# PCB-CCU-IRISCTRL_ETHERMEGA.net
KiCad netlist of a schematic drawn in EAGLE
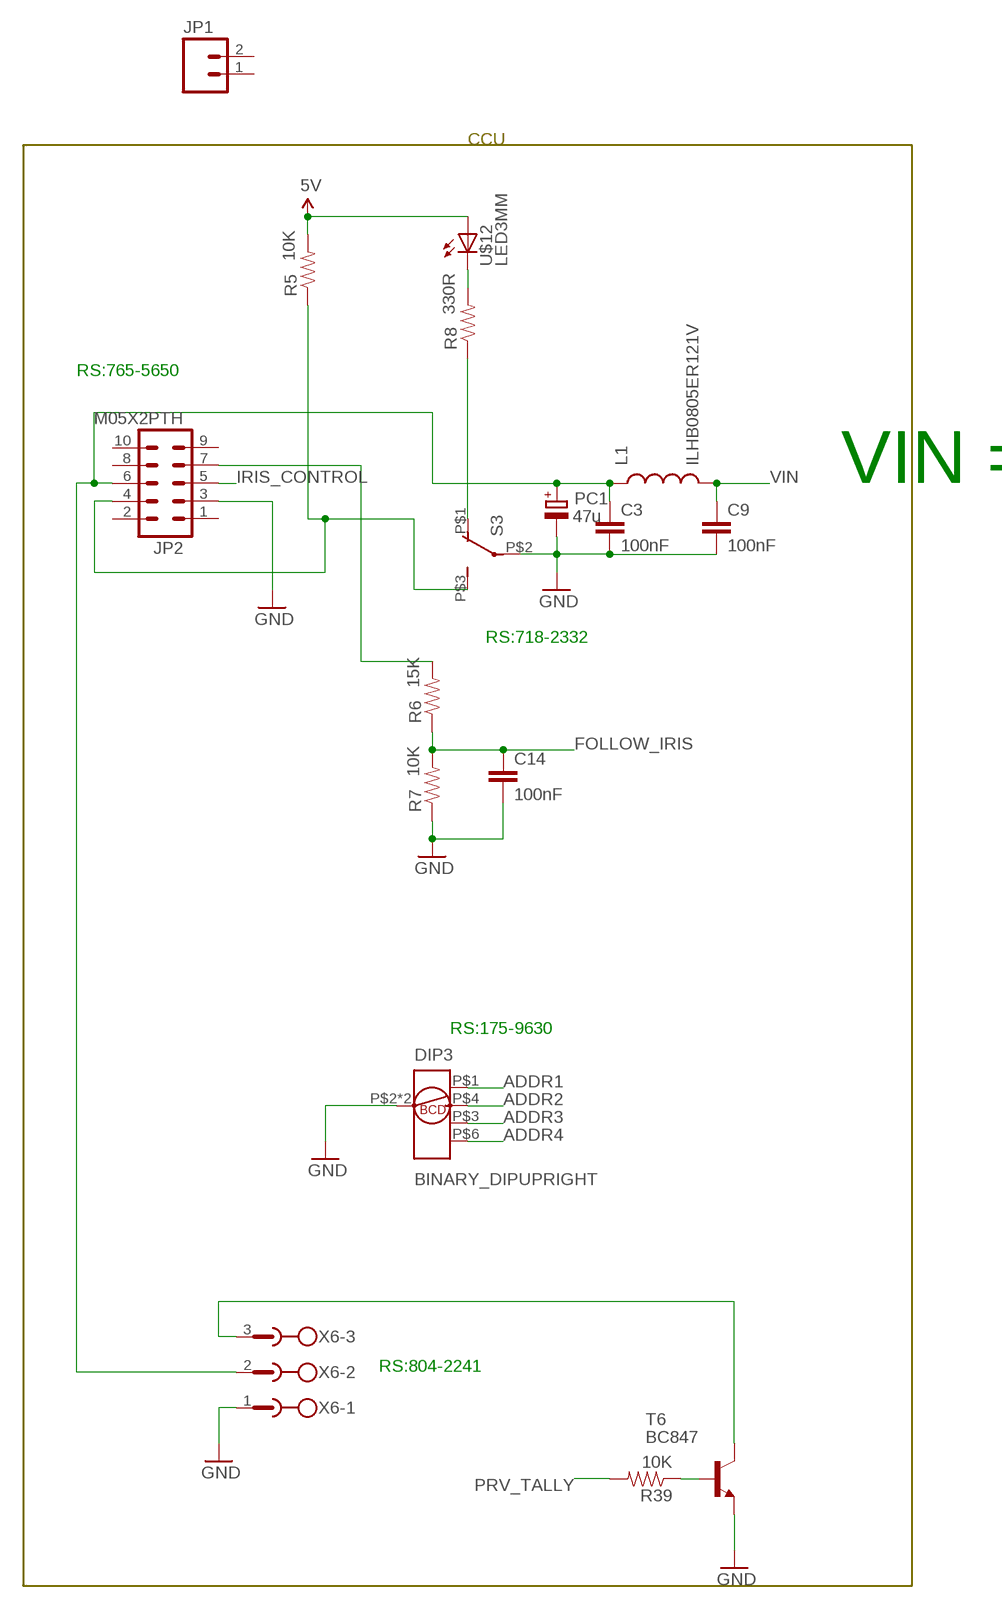
[diagram p0: schematic, sheet 1, part 1 of 3]
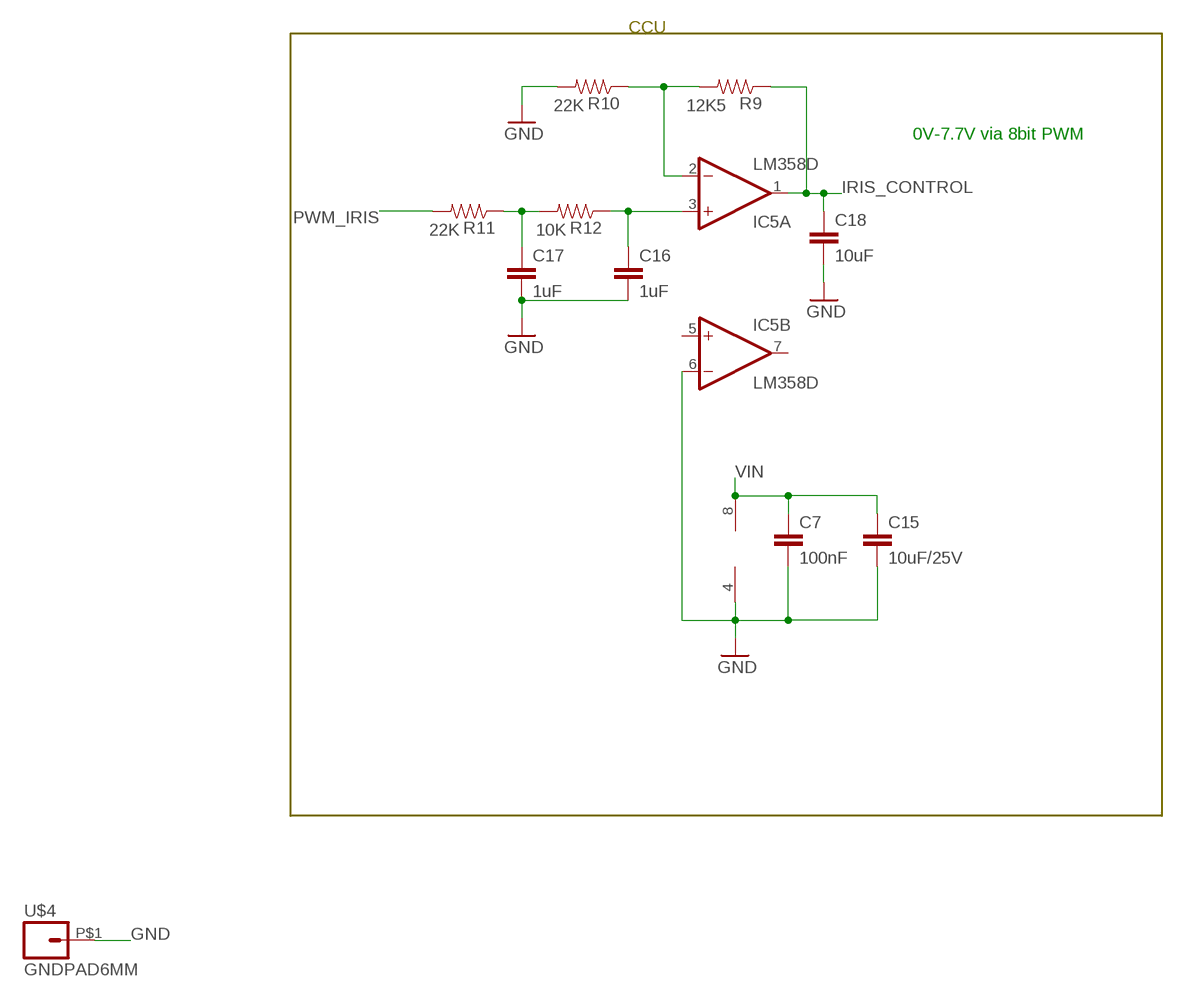
[diagram p1: schematic, sheet 1, part 2 of 3]
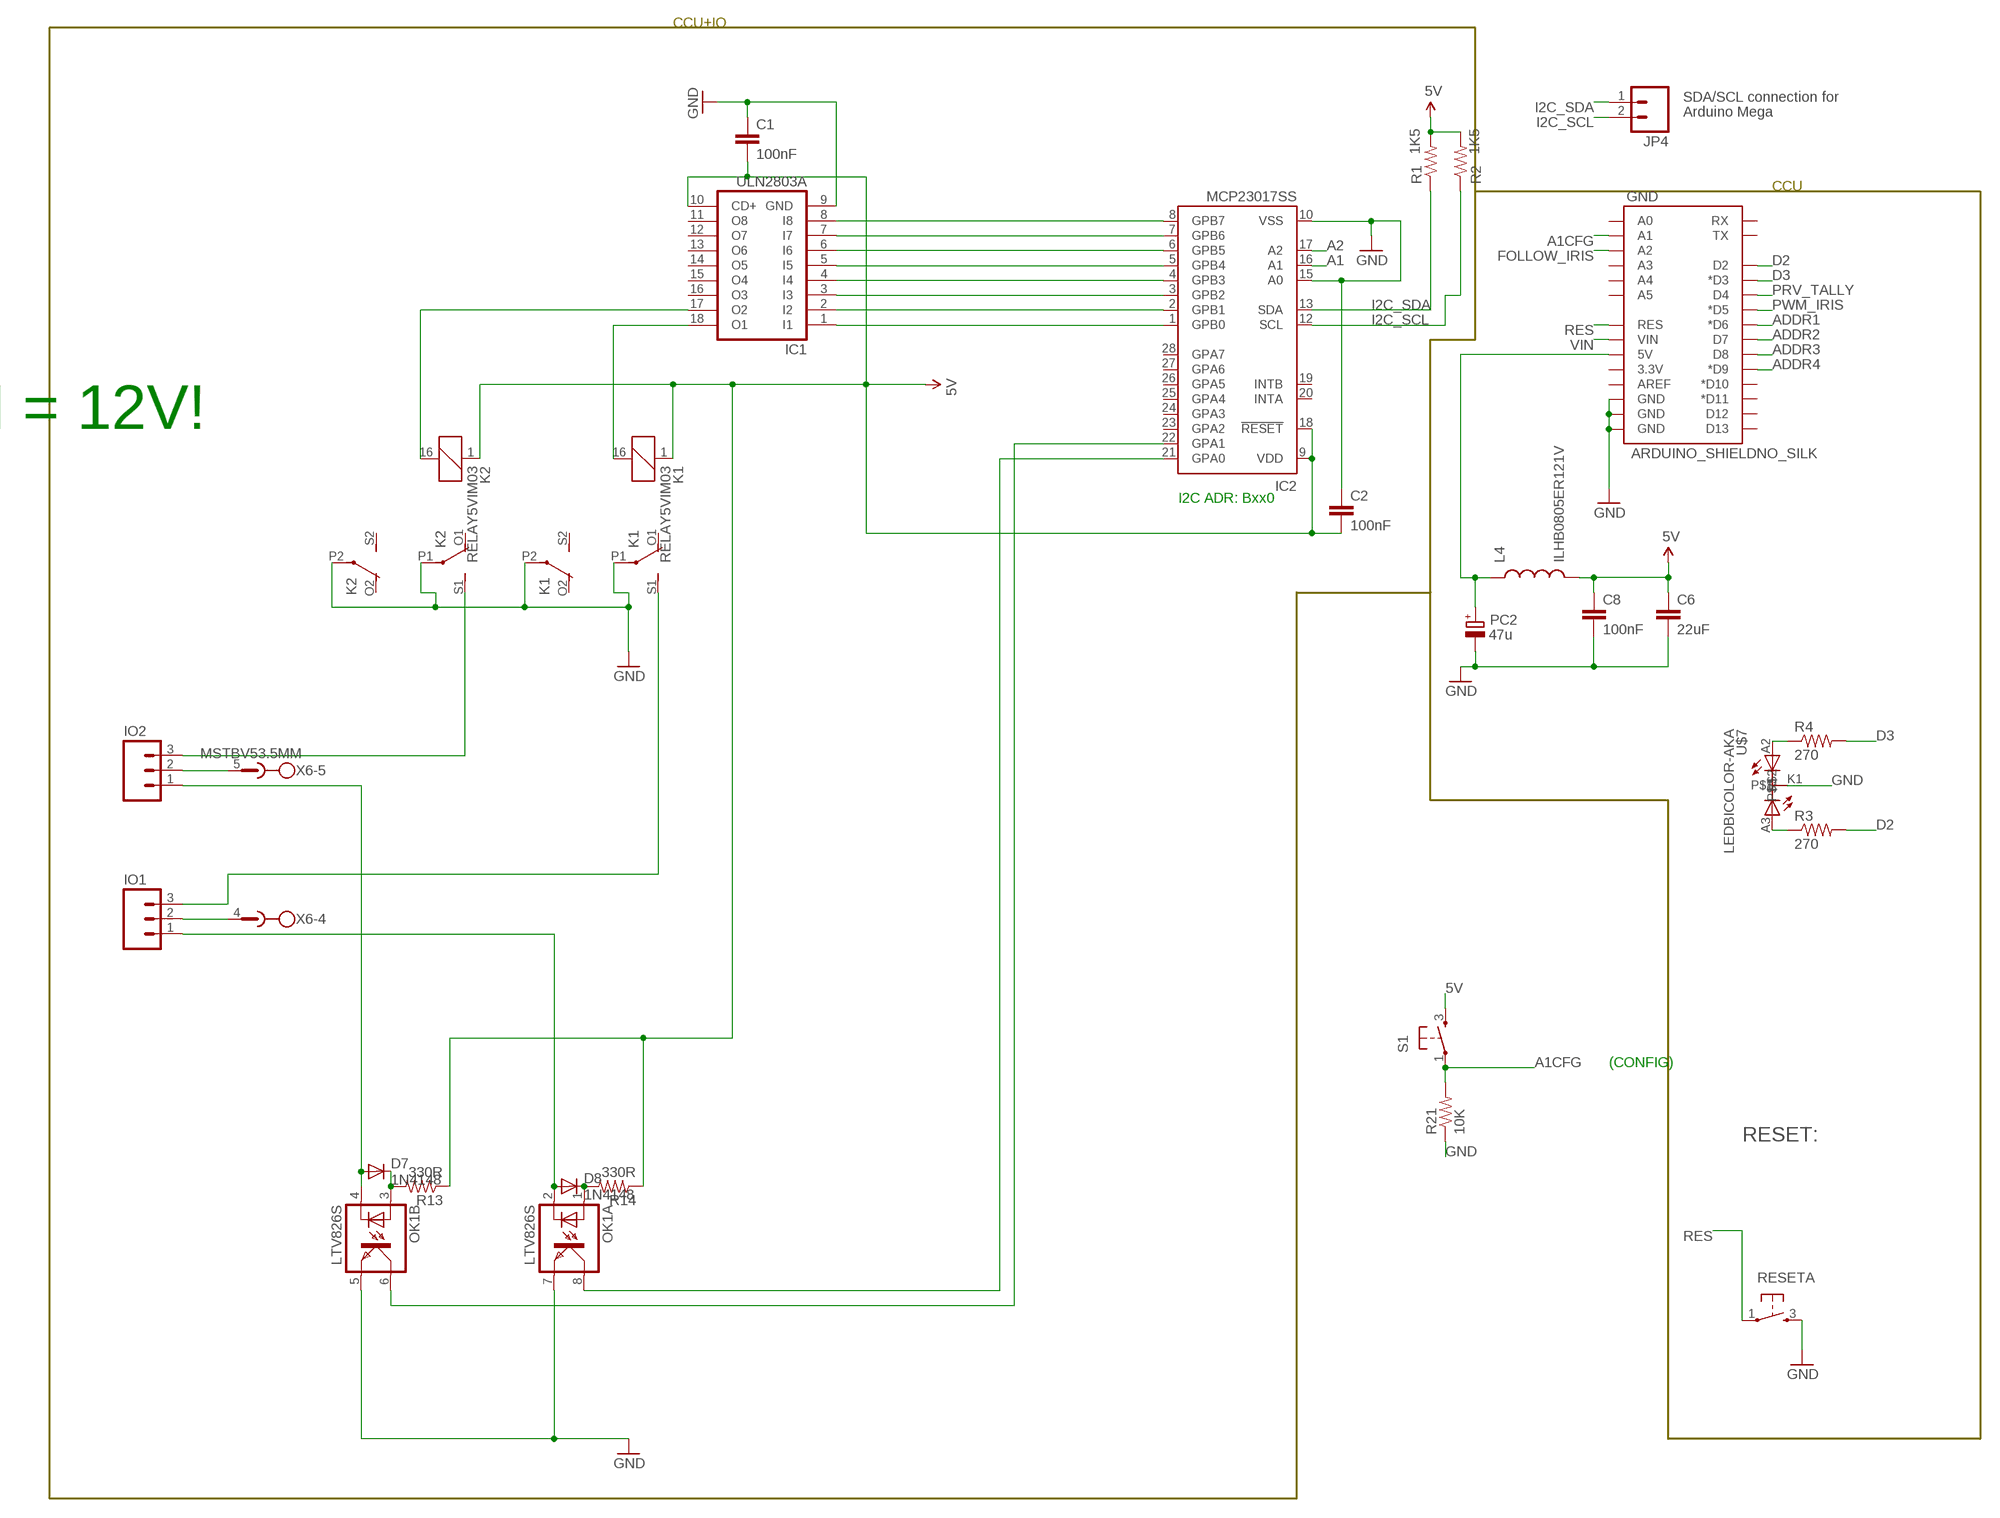
[diagram p2: schematic, sheet 1, part 3 of 3]

(export (version "E")
  (design (tool "Eeschema 10.0.6"))
  (components
    (comp (ref "C1")
      (value "100nF")
      (footprint "eagle-import:0805")
      (libsource (lib "eagle-import") (part "CAP0805"))
    )
    (comp (ref "C2")
      (value "100nF")
      (footprint "eagle-import:0603-CAP")
      (libsource (lib "eagle-import") (part "CAP0603-CAP"))
    )
    (comp (ref "C3")
      (value "100nF")
      (footprint "eagle-import:0603-CAP")
      (libsource (lib "eagle-import") (part "CAP0603-CAP"))
    )
    (comp (ref "C6")
      (value "22uF")
      (footprint "eagle-import:0805")
      (libsource (lib "eagle-import") (part "CAP0805"))
    )
    (comp (ref "C7")
      (value "100nF")
      (footprint "eagle-import:0603-CAP")
      (libsource (lib "eagle-import") (part "CAP0603-CAP"))
    )
    (comp (ref "C8")
      (value "100nF")
      (footprint "eagle-import:0603-CAP")
      (libsource (lib "eagle-import") (part "CAP0603-CAP"))
    )
    (comp (ref "C9")
      (value "100nF")
      (footprint "eagle-import:0603-CAP")
      (libsource (lib "eagle-import") (part "CAP0603-CAP"))
    )
    (comp (ref "C14")
      (value "100nF")
      (footprint "eagle-import:0603-CAP")
      (libsource (lib "eagle-import") (part "CAP0603-CAP"))
    )
    (comp (ref "C15")
      (value "10uF/25V")
      (footprint "eagle-import:0805")
      (libsource (lib "eagle-import") (part "CAP0805"))
    )
    (comp (ref "C16")
      (value "1uF")
      (footprint "eagle-import:0805")
      (libsource (lib "eagle-import") (part "CAP0805"))
    )
    (comp (ref "C17")
      (value "1uF")
      (footprint "eagle-import:0805")
      (libsource (lib "eagle-import") (part "CAP0805"))
    )
    (comp (ref "C18")
      (value "10uF")
      (footprint "eagle-import:0805")
      (libsource (lib "eagle-import") (part "CAP0805"))
    )
    (comp (ref "D7")
      (value "1N4148")
      (footprint "eagle-import:SOD-323")
      (libsource (lib "eagle-import") (part "DIODESOD"))
    )
    (comp (ref "D8")
      (value "1N4148")
      (footprint "eagle-import:SOD-323")
      (libsource (lib "eagle-import") (part "DIODESOD"))
    )
    (comp (ref "DIP3")
      (value "BINARY_DIPUPRIGHT")
      (footprint "eagle-import:P65SMT_UPRIGHT_TH")
      (libsource (lib "eagle-import") (part "BINARY_DIPUPRIGHT"))
    )
    (comp (ref "GND")
      (value "ARDUINO_SHIELDNO_SILK")
      (footprint "eagle-import:DUEMILANOVE_VIAS")
      (libsource (lib "eagle-import") (part "ARDUINO_SHIELDNO_SILK"))
    )
    (comp (ref "IC1")
      (value "ULN2803A")
      (footprint "eagle-import:SO18W")
      (libsource (lib "eagle-import") (part "ULN2803ASO18W"))
    )
    (comp (ref "IC2")
      (value "MCP23017SS")
      (footprint "eagle-import:SSOP28")
      (fields (field (name "MF") "MICROCHIP") (field (name "MPN") "MCP23017-E/SS"))
      (libsource (lib "eagle-import") (part "MCP23017SS"))
    )
    (comp (ref "IC5")
      (value "LM358D")
      (footprint "eagle-import:SO08")
      (libsource (lib "eagle-import") (part "LM358D"))
    )
    (comp (ref "IO1")
      (value "M03LOCK")
      (footprint "eagle-import:1X03_LOCK")
      (libsource (lib "eagle-import") (part "M03LOCK"))
    )
    (comp (ref "IO2")
      (value "M03LOCK")
      (footprint "eagle-import:1X03_LOCK")
      (libsource (lib "eagle-import") (part "M03LOCK"))
    )
    (comp (ref "JP1")
      (value "M02PTH")
      (footprint "eagle-import:1X02")
      (libsource (lib "eagle-import") (part "M02PTH"))
    )
    (comp (ref "JP2")
      (value "M05X2PTH")
      (footprint "eagle-import:AVR_ICSP")
      (libsource (lib "eagle-import") (part "M05X2PTH"))
    )
    (comp (ref "JP4")
      (value "M02PTH")
      (footprint "eagle-import:1X02")
      (libsource (lib "eagle-import") (part "M02PTH"))
    )
    (comp (ref "K1")
      (value "RELAY5VIM03")
      (footprint "eagle-import:DS2Y")
      (libsource (lib "eagle-import") (part "RELAY5VIM03"))
    )
    (comp (ref "K2")
      (value "RELAY5VIM03")
      (footprint "eagle-import:DS2Y")
      (libsource (lib "eagle-import") (part "RELAY5VIM03"))
    )
    (comp (ref "L1")
      (value "ILHB0805ER121V")
      (footprint "eagle-import:0805")
      (libsource (lib "eagle-import") (part "INDUCTOR0805"))
    )
    (comp (ref "L4")
      (value "ILHB0805ER121V")
      (footprint "eagle-import:0805")
      (libsource (lib "eagle-import") (part "INDUCTOR0805"))
    )
    (comp (ref "OK1")
      (value "LTV826S")
      (footprint "eagle-import:DIL8-SMD")
      (libsource (lib "eagle-import") (part "LTV826S"))
    )
    (comp (ref "PC1")
      (value "47u")
      (footprint "eagle-import:PANASONIC_D")
      (libsource (lib "eagle-import") (part "CPOL-EUD"))
    )
    (comp (ref "PC2")
      (value "47u")
      (footprint "eagle-import:PANASONIC_D")
      (libsource (lib "eagle-import") (part "CPOL-EUD"))
    )
    (comp (ref "R1")
      (value "1K5")
      (footprint "eagle-import:0603-RES")
      (libsource (lib "eagle-import") (part "RESISTOR0603-RES"))
    )
    (comp (ref "R2")
      (value "1K5")
      (footprint "eagle-import:0603-RES")
      (libsource (lib "eagle-import") (part "RESISTOR0603-RES"))
    )
    (comp (ref "R3")
      (value "270")
      (footprint "eagle-import:0603-RES")
      (libsource (lib "eagle-import") (part "RESISTOR0603-RES"))
    )
    (comp (ref "R4")
      (value "270")
      (footprint "eagle-import:0603-RES")
      (libsource (lib "eagle-import") (part "RESISTOR0603-RES"))
    )
    (comp (ref "R5")
      (value "10K")
      (footprint "eagle-import:0603-RES")
      (libsource (lib "eagle-import") (part "RESISTOR0603-RES"))
    )
    (comp (ref "R6")
      (value "15K")
      (footprint "eagle-import:0603-RES")
      (libsource (lib "eagle-import") (part "RESISTOR0603-RES"))
    )
    (comp (ref "R7")
      (value "10K")
      (footprint "eagle-import:0603-RES")
      (libsource (lib "eagle-import") (part "RESISTOR0603-RES"))
    )
    (comp (ref "R8")
      (value "330R")
      (footprint "eagle-import:0603-RES")
      (libsource (lib "eagle-import") (part "RESISTOR0603-RES"))
    )
    (comp (ref "R9")
      (value "12K5")
      (footprint "eagle-import:0603-RES")
      (libsource (lib "eagle-import") (part "RESISTOR0603-RES"))
    )
    (comp (ref "R10")
      (value "22K")
      (footprint "eagle-import:0603-RES")
      (libsource (lib "eagle-import") (part "RESISTOR0603-RES"))
    )
    (comp (ref "R11")
      (value "22K")
      (footprint "eagle-import:0603-RES")
      (libsource (lib "eagle-import") (part "RESISTOR0603-RES"))
    )
    (comp (ref "R12")
      (value "10K")
      (footprint "eagle-import:0603-RES")
      (libsource (lib "eagle-import") (part "RESISTOR0603-RES"))
    )
    (comp (ref "R13")
      (value "330R")
      (footprint "eagle-import:0603-RES")
      (libsource (lib "eagle-import") (part "RESISTOR0603-RES"))
    )
    (comp (ref "R14")
      (value "330R")
      (footprint "eagle-import:0603-RES")
      (libsource (lib "eagle-import") (part "RESISTOR0603-RES"))
    )
    (comp (ref "R21")
      (value "10K")
      (footprint "eagle-import:0603-RES")
      (libsource (lib "eagle-import") (part "RESISTOR0603-RES"))
    )
    (comp (ref "R39")
      (value "10K")
      (footprint "eagle-import:0603-RES")
      (libsource (lib "eagle-import") (part "RESISTOR0603-RES"))
    )
    (comp (ref "RESETA")
      (value "TAC_SWITCH")
      (footprint "eagle-import:PUSHBUTTON")
      (libsource (lib "eagle-import") (part "TAC_SWITCH"))
    )
    (comp (ref "S1")
      (value "TAC_SWITCH")
      (footprint "eagle-import:PUSHBUTTON")
      (libsource (lib "eagle-import") (part "TAC_SWITCH"))
    )
    (comp (ref "S3")
      (value "SWITCH-DPST")
      (footprint "eagle-import:TECONNECTIVITY-DPST")
      (libsource (lib "eagle-import") (part "SWITCH-DPST"))
    )
    (comp (ref "T6")
      (value "BC847")
      (footprint "eagle-import:SOT23")
      (libsource (lib "eagle-import") (part "BC847"))
    )
    (comp (ref "U$4")
      (value "GNDPAD6MM")
      (footprint "eagle-import:3.2MMPAD6MM")
      (libsource (lib "eagle-import") (part "GNDPAD6MM"))
    )
    (comp (ref "U$7")
      (value "LEDBICOLOR-AKA")
      (footprint "eagle-import:LED5MM-BICOLOR")
      (libsource (lib "eagle-import") (part "LEDBICOLOR-AKA"))
    )
    (comp (ref "U$12")
      (value "LED3MM")
      (footprint "eagle-import:LED3MM")
      (libsource (lib "eagle-import") (part "LED3MM"))
    )
    (comp (ref "X6")
      (value "MSTBV53.5MM")
      (footprint "eagle-import:MSTBV5-3.5")
      (libsource (lib "eagle-import") (part "MSTBV53.5MM"))
    )
  )
  (nets
    (net (code "1") (name "5V") (class "Default")
      (node (ref "C1") (pin "2") (pinfunction "2_2") (pintype "passive"))
      (node (ref "C2") (pin "2") (pinfunction "2_2") (pintype "passive"))
      (node (ref "C6") (pin "1") (pinfunction "1_1") (pintype "passive"))
      (node (ref "C8") (pin "1") (pinfunction "1_1") (pintype "passive"))
      (node (ref "IC1") (pin "10") (pinfunction "CD+_10") (pintype "passive"))
      (node (ref "IC2") (pin "18") (pinfunction "~{RESET}_18") (pintype "input"))
      (node (ref "IC2") (pin "9") (pinfunction "VDD_9") (pintype "power_in"))
      (node (ref "K1") (pin "1") (pinfunction "1_1") (pintype "passive"))
      (node (ref "K2") (pin "1") (pinfunction "1_1") (pintype "passive"))
      (node (ref "L4") (pin "2") (pinfunction "2_2") (pintype "passive"))
      (node (ref "R1") (pin "2") (pinfunction "2_2") (pintype "passive"))
      (node (ref "R13") (pin "1") (pinfunction "1_1") (pintype "passive"))
      (node (ref "R14") (pin "1") (pinfunction "1_1") (pintype "passive"))
      (node (ref "R2") (pin "2") (pinfunction "2_2") (pintype "passive"))
      (node (ref "R5") (pin "2") (pinfunction "2_2") (pintype "passive"))
      (node (ref "S1") (pin "3") (pinfunction "3_3") (pintype "passive"))
      (node (ref "U$12") (pin "A") (pinfunction "A_A") (pintype "passive"))
    )
    (net (code "2") (name "A1") (class "Default")
      (node (ref "IC2") (pin "16") (pinfunction "A1_16") (pintype "input"))
    )
    (net (code "3") (name "A1CFG") (class "Default")
      (node (ref "GND") (pin "A1") (pinfunction "A1_A1") (pintype "bidirectional"))
      (node (ref "R21") (pin "2") (pinfunction "2_2") (pintype "passive"))
      (node (ref "S1") (pin "1") (pinfunction "1_1") (pintype "passive"))
    )
    (net (code "4") (name "A2") (class "Default")
      (node (ref "IC2") (pin "17") (pinfunction "A2_17") (pintype "input"))
    )
    (net (code "5") (name "ADDR1") (class "Default")
      (node (ref "DIP3") (pin "P$1") (pinfunction "1_P$1") (pintype "passive"))
      (node (ref "GND") (pin "D6") (pinfunction "*D6_D6") (pintype "bidirectional"))
    )
    (net (code "6") (name "ADDR2") (class "Default")
      (node (ref "DIP3") (pin "P$4") (pinfunction "2_P$4") (pintype "passive"))
      (node (ref "GND") (pin "D7") (pinfunction "D7_D7") (pintype "bidirectional"))
    )
    (net (code "7") (name "ADDR3") (class "Default")
      (node (ref "DIP3") (pin "P$3") (pinfunction "4_P$3") (pintype "passive"))
      (node (ref "GND") (pin "D8") (pinfunction "D8_D8") (pintype "bidirectional"))
    )
    (net (code "8") (name "ADDR4") (class "Default")
      (node (ref "DIP3") (pin "P$6") (pinfunction "8_P$6") (pintype "passive"))
      (node (ref "GND") (pin "D9") (pinfunction "*D9_D9") (pintype "bidirectional"))
    )
    (net (code "9") (name "D2") (class "Default")
      (node (ref "GND") (pin "D2") (pinfunction "D2_D2") (pintype "bidirectional"))
      (node (ref "R3") (pin "2") (pinfunction "2_2") (pintype "passive"))
    )
    (net (code "10") (name "D3") (class "Default")
      (node (ref "GND") (pin "D3") (pinfunction "*D3_D3") (pintype "bidirectional"))
      (node (ref "R4") (pin "2") (pinfunction "2_2") (pintype "passive"))
    )
    (net (code "11") (name "FOLLOW_IRIS") (class "Default")
      (node (ref "C14") (pin "1") (pinfunction "1_1") (pintype "passive"))
      (node (ref "GND") (pin "A2") (pinfunction "A2_A2") (pintype "bidirectional"))
      (node (ref "R6") (pin "1") (pinfunction "1_1") (pintype "passive"))
      (node (ref "R7") (pin "2") (pinfunction "2_2") (pintype "passive"))
    )
    (net (code "12") (name "GND") (class "Default")
      (node (ref "C1") (pin "1") (pinfunction "1_1") (pintype "passive"))
      (node (ref "C14") (pin "2") (pinfunction "2_2") (pintype "passive"))
      (node (ref "C15") (pin "2") (pinfunction "2_2") (pintype "passive"))
      (node (ref "C16") (pin "2") (pinfunction "2_2") (pintype "passive"))
      (node (ref "C17") (pin "2") (pinfunction "2_2") (pintype "passive"))
      (node (ref "C18") (pin "2") (pinfunction "2_2") (pintype "passive"))
      (node (ref "C2") (pin "1") (pinfunction "1_1") (pintype "passive"))
      (node (ref "C3") (pin "2") (pinfunction "2_2") (pintype "passive"))
      (node (ref "C6") (pin "2") (pinfunction "2_2") (pintype "passive"))
      (node (ref "C7") (pin "2") (pinfunction "2_2") (pintype "passive"))
      (node (ref "C8") (pin "2") (pinfunction "2_2") (pintype "passive"))
      (node (ref "C9") (pin "2") (pinfunction "2_2") (pintype "passive"))
      (node (ref "DIP3") (pin "P$2") (pinfunction "GND_P$2") (pintype "passive"))
      (node (ref "DIP3") (pin "P$5") (pinfunction "GND_P$5") (pintype "passive"))
      (node (ref "GND") (pin "GND@0") (pinfunction "GND_GND@0") (pintype "bidirectional"))
      (node (ref "GND") (pin "GND@1") (pinfunction "GND_GND@1") (pintype "bidirectional"))
      (node (ref "GND") (pin "GND@2") (pinfunction "GND_GND@2") (pintype "bidirectional"))
      (node (ref "IC1") (pin "9") (pinfunction "GND_9") (pintype "power_in"))
      (node (ref "IC2") (pin "10") (pinfunction "VSS_10") (pintype "power_in"))
      (node (ref "IC2") (pin "15") (pinfunction "A0_15") (pintype "input"))
      (node (ref "IC5") (pin "4") (pinfunction "V-_4") (pintype "power_in"))
      (node (ref "IC5") (pin "6") (pinfunction "-IN_6") (pintype "input"))
      (node (ref "JP2") (pin "3") (pinfunction "3_3") (pintype "passive"))
      (node (ref "K1") (pin "P1") (pinfunction "P_P1") (pintype "passive"))
      (node (ref "K1") (pin "P2") (pinfunction "P_P2") (pintype "passive"))
      (node (ref "K2") (pin "P1") (pinfunction "P_P1") (pintype "passive"))
      (node (ref "K2") (pin "P2") (pinfunction "P_P2") (pintype "passive"))
      (node (ref "OK1") (pin "5") (pinfunction "EMIT_5") (pintype "passive"))
      (node (ref "OK1") (pin "7") (pinfunction "EMIT_7") (pintype "passive"))
      (node (ref "PC1") (pin "-") (pinfunction "-_-") (pintype "passive"))
      (node (ref "PC2") (pin "-") (pinfunction "-_-") (pintype "passive"))
      (node (ref "R10") (pin "2") (pinfunction "2_2") (pintype "passive"))
      (node (ref "R21") (pin "1") (pinfunction "1_1") (pintype "passive"))
      (node (ref "R7") (pin "1") (pinfunction "1_1") (pintype "passive"))
      (node (ref "RESETA") (pin "3") (pinfunction "3_3") (pintype "passive"))
      (node (ref "S3") (pin "P$2") (pinfunction "P_P$2") (pintype "passive"))
      (node (ref "T6") (pin "2") (pinfunction "E_2") (pintype "passive"))
      (node (ref "U$4") (pin "P$1") (pinfunction "1_P$1") (pintype "passive"))
      (node (ref "U$7") (pin "K1") (pinfunction "P$1_K1") (pintype "bidirectional"))
      (node (ref "X6") (pin "1") (pinfunction "1_1") (pintype "passive"))
    )
    (net (code "13") (name "I2C_SCL") (class "Default")
      (node (ref "IC2") (pin "12") (pinfunction "SCL_12") (pintype "input"))
      (node (ref "JP4") (pin "2") (pinfunction "2_2") (pintype "passive"))
      (node (ref "R2") (pin "1") (pinfunction "1_1") (pintype "passive"))
    )
    (net (code "14") (name "I2C_SDA") (class "Default")
      (node (ref "IC2") (pin "13") (pinfunction "SDA_13") (pintype "bidirectional"))
      (node (ref "JP4") (pin "1") (pinfunction "1_1") (pintype "passive"))
      (node (ref "R1") (pin "1") (pinfunction "1_1") (pintype "passive"))
    )
    (net (code "15") (name "IRIS_CONTROL") (class "Default")
      (node (ref "C18") (pin "1") (pinfunction "1_1") (pintype "passive"))
      (node (ref "IC5") (pin "1") (pinfunction "OUT_1") (pintype "output"))
      (node (ref "JP2") (pin "5") (pinfunction "5_5") (pintype "passive"))
      (node (ref "R9") (pin "1") (pinfunction "1_1") (pintype "passive"))
    )
    (net (code "16") (name "Net-(C17-Pad1)") (class "Default")
      (node (ref "C17") (pin "1") (pinfunction "1_1") (pintype "passive"))
      (node (ref "R11") (pin "1") (pinfunction "1_1") (pintype "passive"))
      (node (ref "R12") (pin "2") (pinfunction "2_2") (pintype "passive"))
    )
    (net (code "17") (name "Net-(D7-A)") (class "Default")
      (node (ref "D7") (pin "2") (pinfunction "A_2") (pintype "passive"))
      (node (ref "IO2") (pin "1") (pinfunction "1_1") (pintype "passive"))
      (node (ref "OK1") (pin "4") (pinfunction "C_4") (pintype "passive"))
    )
    (net (code "18") (name "Net-(D7-C)") (class "Default")
      (node (ref "D7") (pin "1") (pinfunction "C_1") (pintype "passive"))
      (node (ref "OK1") (pin "3") (pinfunction "A_3") (pintype "passive"))
      (node (ref "R13") (pin "2") (pinfunction "2_2") (pintype "passive"))
    )
    (net (code "19") (name "Net-(D8-A)") (class "Default")
      (node (ref "D8") (pin "2") (pinfunction "A_2") (pintype "passive"))
      (node (ref "IO1") (pin "1") (pinfunction "1_1") (pintype "passive"))
      (node (ref "OK1") (pin "2") (pinfunction "C_2") (pintype "passive"))
    )
    (net (code "20") (name "Net-(D8-C)") (class "Default")
      (node (ref "D8") (pin "1") (pinfunction "C_1") (pintype "passive"))
      (node (ref "OK1") (pin "1") (pinfunction "A_1") (pintype "passive"))
      (node (ref "R14") (pin "2") (pinfunction "2_2") (pintype "passive"))
    )
    (net (code "21") (name "Net-(GND-Pad5V)") (class "Default")
      (node (ref "GND") (pin "5V") (pinfunction "5V_5V") (pintype "bidirectional"))
      (node (ref "L4") (pin "1") (pinfunction "1_1") (pintype "passive"))
      (node (ref "PC2") (pin "+") (pinfunction "+_+") (pintype "passive"))
    )
    (net (code "22") (name "Net-(IC1-I1)") (class "Default")
      (node (ref "IC1") (pin "1") (pinfunction "I1_1") (pintype "input"))
      (node (ref "IC2") (pin "1") (pinfunction "GPB0_1") (pintype "bidirectional"))
    )
    (net (code "23") (name "Net-(IC1-I2)") (class "Default")
      (node (ref "IC1") (pin "2") (pinfunction "I2_2") (pintype "input"))
      (node (ref "IC2") (pin "2") (pinfunction "GPB1_2") (pintype "bidirectional"))
    )
    (net (code "24") (name "Net-(IC1-I3)") (class "Default")
      (node (ref "IC1") (pin "3") (pinfunction "I3_3") (pintype "input"))
      (node (ref "IC2") (pin "3") (pinfunction "GPB2_3") (pintype "bidirectional"))
    )
    (net (code "25") (name "Net-(IC1-I4)") (class "Default")
      (node (ref "IC1") (pin "4") (pinfunction "I4_4") (pintype "input"))
      (node (ref "IC2") (pin "4") (pinfunction "GPB3_4") (pintype "bidirectional"))
    )
    (net (code "26") (name "Net-(IC1-I5)") (class "Default")
      (node (ref "IC1") (pin "5") (pinfunction "I5_5") (pintype "input"))
      (node (ref "IC2") (pin "5") (pinfunction "GPB4_5") (pintype "bidirectional"))
    )
    (net (code "27") (name "Net-(IC1-I6)") (class "Default")
      (node (ref "IC1") (pin "6") (pinfunction "I6_6") (pintype "input"))
      (node (ref "IC2") (pin "6") (pinfunction "GPB5_6") (pintype "bidirectional"))
    )
    (net (code "28") (name "Net-(IC1-I7)") (class "Default")
      (node (ref "IC1") (pin "7") (pinfunction "I7_7") (pintype "input"))
      (node (ref "IC2") (pin "7") (pinfunction "GPB6_7") (pintype "bidirectional"))
    )
    (net (code "29") (name "Net-(IC1-I8)") (class "Default")
      (node (ref "IC1") (pin "8") (pinfunction "I8_8") (pintype "input"))
      (node (ref "IC2") (pin "8") (pinfunction "GPB7_8") (pintype "bidirectional"))
    )
    (net (code "30") (name "Net-(IC1-O1)") (class "Default")
      (node (ref "IC1") (pin "18") (pinfunction "O1_18") (pintype "open_collector"))
      (node (ref "K1") (pin "16") (pinfunction "2_16") (pintype "passive"))
    )
    (net (code "31") (name "Net-(IC1-O2)") (class "Default")
      (node (ref "IC1") (pin "17") (pinfunction "O2_17") (pintype "open_collector"))
      (node (ref "K2") (pin "16") (pinfunction "2_16") (pintype "passive"))
    )
    (net (code "32") (name "Net-(IC2-GPA0)") (class "Default")
      (node (ref "IC2") (pin "21") (pinfunction "GPA0_21") (pintype "bidirectional"))
      (node (ref "OK1") (pin "8") (pinfunction "COL_8") (pintype "passive"))
    )
    (net (code "33") (name "Net-(IC2-GPA1)") (class "Default")
      (node (ref "IC2") (pin "22") (pinfunction "GPA1_22") (pintype "bidirectional"))
      (node (ref "OK1") (pin "6") (pinfunction "COL_6") (pintype "passive"))
    )
    (net (code "34") (name "Net-(IC5A-+IN)") (class "Default")
      (node (ref "C16") (pin "1") (pinfunction "1_1") (pintype "passive"))
      (node (ref "IC5") (pin "3") (pinfunction "+IN_3") (pintype "input"))
      (node (ref "R12") (pin "1") (pinfunction "1_1") (pintype "passive"))
    )
    (net (code "35") (name "Net-(IC5A--IN)") (class "Default")
      (node (ref "IC5") (pin "2") (pinfunction "-IN_2") (pintype "input"))
      (node (ref "R10") (pin "1") (pinfunction "1_1") (pintype "passive"))
      (node (ref "R9") (pin "2") (pinfunction "2_2") (pintype "passive"))
    )
    (net (code "36") (name "Net-(JP2-Pad7)") (class "Default")
      (node (ref "JP2") (pin "7") (pinfunction "7_7") (pintype "passive"))
      (node (ref "R6") (pin "2") (pinfunction "2_2") (pintype "passive"))
    )
    (net (code "37") (name "Net-(K1B-S)") (class "Default")
      (node (ref "IO1") (pin "3") (pinfunction "3_3") (pintype "passive"))
      (node (ref "K1") (pin "S1") (pinfunction "S_S1") (pintype "passive"))
    )
    (net (code "38") (name "Net-(K2B-S)") (class "Default")
      (node (ref "IO2") (pin "3") (pinfunction "3_3") (pintype "passive"))
      (node (ref "K2") (pin "S1") (pinfunction "S_S1") (pintype "passive"))
    )
    (net (code "39") (name "Net-(S3-O)") (class "Default")
      (node (ref "R8") (pin "1") (pinfunction "1_1") (pintype "passive"))
      (node (ref "S3") (pin "P$1") (pinfunction "O_P$1") (pintype "passive"))
    )
    (net (code "40") (name "Net-(S3-S)") (class "Default")
      (node (ref "JP2") (pin "4") (pinfunction "4_4") (pintype "passive"))
      (node (ref "R5") (pin "1") (pinfunction "1_1") (pintype "passive"))
      (node (ref "S3") (pin "P$3") (pinfunction "S_P$3") (pintype "passive"))
    )
    (net (code "41") (name "Net-(T6-B)") (class "Default")
      (node (ref "R39") (pin "1") (pinfunction "1_1") (pintype "passive"))
      (node (ref "T6") (pin "1") (pinfunction "B_1") (pintype "passive"))
    )
    (net (code "42") (name "Net-(T6-C)") (class "Default")
      (node (ref "T6") (pin "3") (pinfunction "C_3") (pintype "passive"))
      (node (ref "X6") (pin "3") (pinfunction "1_3") (pintype "passive"))
    )
    (net (code "43") (name "Net-(U$7-P$2)") (class "Default")
      (node (ref "R4") (pin "1") (pinfunction "1_1") (pintype "passive"))
      (node (ref "U$7") (pin "A2") (pinfunction "P$2_A2") (pintype "bidirectional"))
    )
    (net (code "44") (name "Net-(U$7-P$3)") (class "Default")
      (node (ref "R3") (pin "1") (pinfunction "1_1") (pintype "passive"))
      (node (ref "U$7") (pin "A3") (pinfunction "P$3_A3") (pintype "bidirectional"))
    )
    (net (code "45") (name "Net-(U$12-C)") (class "Default")
      (node (ref "R8") (pin "2") (pinfunction "2_2") (pintype "passive"))
      (node (ref "U$12") (pin "K") (pinfunction "C_K") (pintype "passive"))
    )
    (net (code "46") (name "Net-(X6B-1)") (class "Default")
      (node (ref "C3") (pin "1") (pinfunction "1_1") (pintype "passive"))
      (node (ref "JP2") (pin "6") (pinfunction "6_6") (pintype "passive"))
      (node (ref "L1") (pin "1") (pinfunction "1_1") (pintype "passive"))
      (node (ref "PC1") (pin "+") (pinfunction "+_+") (pintype "passive"))
      (node (ref "X6") (pin "2") (pinfunction "1_2") (pintype "passive"))
    )
    (net (code "47") (name "Net-(X6D-1)") (class "Default")
      (node (ref "IO1") (pin "2") (pinfunction "2_2") (pintype "passive"))
      (node (ref "X6") (pin "4") (pinfunction "1_4") (pintype "passive"))
    )
    (net (code "48") (name "Net-(X6E-1)") (class "Default")
      (node (ref "IO2") (pin "2") (pinfunction "2_2") (pintype "passive"))
      (node (ref "X6") (pin "5") (pinfunction "1_5") (pintype "passive"))
    )
    (net (code "49") (name "PRV_TALLY") (class "Default")
      (node (ref "GND") (pin "D4") (pinfunction "D4_D4") (pintype "bidirectional"))
      (node (ref "R39") (pin "2") (pinfunction "2_2") (pintype "passive"))
    )
    (net (code "50") (name "PWM_IRIS") (class "Default")
      (node (ref "GND") (pin "D5") (pinfunction "*D5_D5") (pintype "bidirectional"))
      (node (ref "R11") (pin "2") (pinfunction "2_2") (pintype "passive"))
    )
    (net (code "51") (name "RES") (class "Default")
      (node (ref "GND") (pin "RES") (pinfunction "RES_RES") (pintype "bidirectional"))
      (node (ref "RESETA") (pin "1") (pinfunction "1_1") (pintype "passive"))
    )
    (net (code "52") (name "VIN") (class "Default")
      (node (ref "C15") (pin "1") (pinfunction "1_1") (pintype "passive"))
      (node (ref "C7") (pin "1") (pinfunction "1_1") (pintype "passive"))
      (node (ref "C9") (pin "1") (pinfunction "1_1") (pintype "passive"))
      (node (ref "GND") (pin "VIN") (pinfunction "VIN_VIN") (pintype "bidirectional"))
      (node (ref "IC5") (pin "8") (pinfunction "V+_8") (pintype "power_in"))
      (node (ref "L1") (pin "2") (pinfunction "2_2") (pintype "passive"))
    )
    (net (code "53") (name "unconnected-(GND-*D10-PadD10)") (class "Default")
      (node (ref "GND") (pin "D10") (pinfunction "*D10_D10") (pintype "bidirectional"))
    )
    (net (code "54") (name "unconnected-(GND-*D11-PadD11)") (class "Default")
      (node (ref "GND") (pin "D11") (pinfunction "*D11_D11") (pintype "bidirectional"))
    )
    (net (code "55") (name "unconnected-(GND-Pad3.3V)") (class "Default")
      (node (ref "GND") (pin "3.3V") (pinfunction "3.3V_3.3V") (pintype "bidirectional"))
    )
    (net (code "56") (name "unconnected-(GND-PadA0)") (class "Default")
      (node (ref "GND") (pin "A0") (pinfunction "A0_A0") (pintype "bidirectional"))
    )
    (net (code "57") (name "unconnected-(GND-PadA3)") (class "Default")
      (node (ref "GND") (pin "A3") (pinfunction "A3_A3") (pintype "bidirectional"))
    )
    (net (code "58") (name "unconnected-(GND-PadA4)") (class "Default")
      (node (ref "GND") (pin "A4") (pinfunction "A4_A4") (pintype "bidirectional"))
    )
    (net (code "59") (name "unconnected-(GND-PadA5)") (class "Default")
      (node (ref "GND") (pin "A5") (pinfunction "A5_A5") (pintype "bidirectional"))
    )
    (net (code "60") (name "unconnected-(GND-PadAREF)") (class "Default")
      (node (ref "GND") (pin "AREF") (pinfunction "AREF_AREF") (pintype "bidirectional"))
    )
    (net (code "61") (name "unconnected-(GND-PadD12)") (class "Default")
      (node (ref "GND") (pin "D12") (pinfunction "D12_D12") (pintype "bidirectional"))
    )
    (net (code "62") (name "unconnected-(GND-PadD13)") (class "Default")
      (node (ref "GND") (pin "D13") (pinfunction "D13_D13") (pintype "bidirectional"))
    )
    (net (code "63") (name "unconnected-(GND-PadRX)") (class "Default")
      (node (ref "GND") (pin "RX") (pinfunction "RX_RX") (pintype "bidirectional"))
    )
    (net (code "64") (name "unconnected-(GND-PadTX)") (class "Default")
      (node (ref "GND") (pin "TX") (pinfunction "TX_TX") (pintype "bidirectional"))
    )
    (net (code "65") (name "unconnected-(IC1-O3-Pad16)") (class "Default")
      (node (ref "IC1") (pin "16") (pinfunction "O3_16") (pintype "open_collector"))
    )
    (net (code "66") (name "unconnected-(IC1-O4-Pad15)") (class "Default")
      (node (ref "IC1") (pin "15") (pinfunction "O4_15") (pintype "open_collector"))
    )
    (net (code "67") (name "unconnected-(IC1-O5-Pad14)") (class "Default")
      (node (ref "IC1") (pin "14") (pinfunction "O5_14") (pintype "open_collector"))
    )
    (net (code "68") (name "unconnected-(IC1-O6-Pad13)") (class "Default")
      (node (ref "IC1") (pin "13") (pinfunction "O6_13") (pintype "open_collector"))
    )
    (net (code "69") (name "unconnected-(IC1-O7-Pad12)") (class "Default")
      (node (ref "IC1") (pin "12") (pinfunction "O7_12") (pintype "open_collector"))
    )
    (net (code "70") (name "unconnected-(IC1-O8-Pad11)") (class "Default")
      (node (ref "IC1") (pin "11") (pinfunction "O8_11") (pintype "open_collector"))
    )
    (net (code "71") (name "unconnected-(IC2-GPA2-Pad23)") (class "Default")
      (node (ref "IC2") (pin "23") (pinfunction "GPA2_23") (pintype "bidirectional"))
    )
    (net (code "72") (name "unconnected-(IC2-GPA3-Pad24)") (class "Default")
      (node (ref "IC2") (pin "24") (pinfunction "GPA3_24") (pintype "bidirectional"))
    )
    (net (code "73") (name "unconnected-(IC2-GPA4-Pad25)") (class "Default")
      (node (ref "IC2") (pin "25") (pinfunction "GPA4_25") (pintype "bidirectional"))
    )
    (net (code "74") (name "unconnected-(IC2-GPA5-Pad26)") (class "Default")
      (node (ref "IC2") (pin "26") (pinfunction "GPA5_26") (pintype "bidirectional"))
    )
    (net (code "75") (name "unconnected-(IC2-GPA6-Pad27)") (class "Default")
      (node (ref "IC2") (pin "27") (pinfunction "GPA6_27") (pintype "bidirectional"))
    )
    (net (code "76") (name "unconnected-(IC2-GPA7-Pad28)") (class "Default")
      (node (ref "IC2") (pin "28") (pinfunction "GPA7_28") (pintype "bidirectional"))
    )
    (net (code "77") (name "unconnected-(IC2-INTA-Pad20)") (class "Default")
      (node (ref "IC2") (pin "20") (pinfunction "INTA_20") (pintype "output"))
    )
    (net (code "78") (name "unconnected-(IC2-INTB-Pad19)") (class "Default")
      (node (ref "IC2") (pin "19") (pinfunction "INTB_19") (pintype "output"))
    )
    (net (code "79") (name "unconnected-(IC5B-+IN-Pad5)") (class "Default")
      (node (ref "IC5") (pin "5") (pinfunction "+IN_5") (pintype "input"))
    )
    (net (code "80") (name "unconnected-(IC5B-OUT-Pad7)") (class "Default")
      (node (ref "IC5") (pin "7") (pinfunction "OUT_7") (pintype "output"))
    )
    (net (code "81") (name "unconnected-(JP1-Pad1)") (class "Default")
      (node (ref "JP1") (pin "1") (pinfunction "1_1") (pintype "passive"))
    )
    (net (code "82") (name "unconnected-(JP1-Pad2)") (class "Default")
      (node (ref "JP1") (pin "2") (pinfunction "2_2") (pintype "passive"))
    )
    (net (code "83") (name "unconnected-(JP2-Pad1)") (class "Default")
      (node (ref "JP2") (pin "1") (pinfunction "1_1") (pintype "passive"))
    )
    (net (code "84") (name "unconnected-(JP2-Pad2)") (class "Default")
      (node (ref "JP2") (pin "2") (pinfunction "2_2") (pintype "passive"))
    )
    (net (code "85") (name "unconnected-(JP2-Pad8)") (class "Default")
      (node (ref "JP2") (pin "8") (pinfunction "8_8") (pintype "passive"))
    )
    (net (code "86") (name "unconnected-(JP2-Pad9)") (class "Default")
      (node (ref "JP2") (pin "9") (pinfunction "9_9") (pintype "passive"))
    )
    (net (code "87") (name "unconnected-(JP2-Pad10)") (class "Default")
      (node (ref "JP2") (pin "10") (pinfunction "10_10") (pintype "passive"))
    )
    (net (code "88") (name "unconnected-(K1B-O-PadO1)") (class "Default")
      (node (ref "K1") (pin "O1") (pinfunction "O_O1") (pintype "passive"))
    )
    (net (code "89") (name "unconnected-(K1C-O-PadO2)") (class "Default")
      (node (ref "K1") (pin "O2") (pinfunction "O_O2") (pintype "passive"))
    )
    (net (code "90") (name "unconnected-(K1C-S-PadS2)") (class "Default")
      (node (ref "K1") (pin "S2") (pinfunction "S_S2") (pintype "passive"))
    )
    (net (code "91") (name "unconnected-(K2B-O-PadO1)") (class "Default")
      (node (ref "K2") (pin "O1") (pinfunction "O_O1") (pintype "passive"))
    )
    (net (code "92") (name "unconnected-(K2C-O-PadO2)") (class "Default")
      (node (ref "K2") (pin "O2") (pinfunction "O_O2") (pintype "passive"))
    )
    (net (code "93") (name "unconnected-(K2C-S-PadS2)") (class "Default")
      (node (ref "K2") (pin "S2") (pinfunction "S_S2") (pintype "passive"))
    )
  )
)
